# Audio_Video_Router.net
KiCad netlist of a schematic drawn in Altium Designer
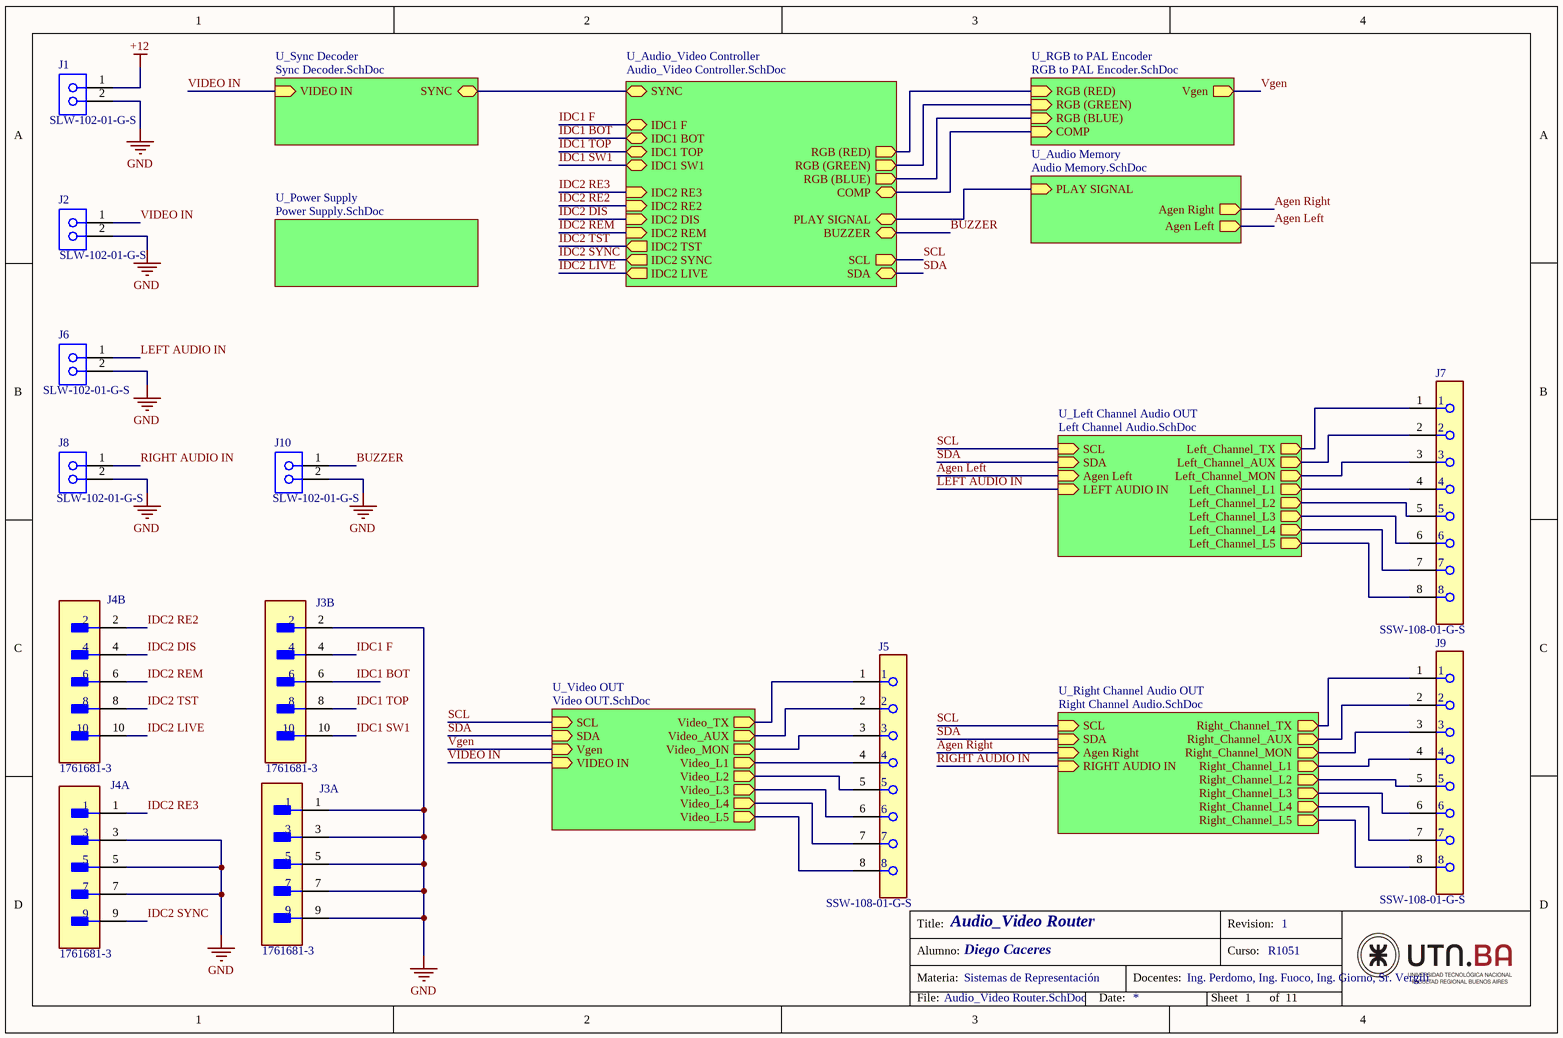
[diagram p0: Audio_Video Router.SchDoc]

(export (version "E")
  (design (tool "Eeschema 10.0.6"))
  (components
    (comp (ref "J1")
      (value "SLW-102-01-G-S")
      (footprint "SMTC-SLW-102-01-X-S")
      (fields (field (name "MANUFACTURER") "Samtec"))
      (libsource (lib "Altium Content Vault") (part "SMTC-SLW-102-01-X-S"))
    )
    (comp (ref "J2")
      (value "SLW-102-01-G-S")
      (footprint "SMTC-SLW-102-01-X-S")
      (fields (field (name "MANUFACTURER") "Samtec"))
      (libsource (lib "Altium Content Vault") (part "SMTC-SLW-102-01-X-S"))
    )
    (comp (ref "J3")
      (value "1761681-3")
      (footprint "FP-1761681-3-MFG")
      (description "1761681-3 Conn Shrouded Header (4 Sides) HDR 10 POS 2.54mm Solder ST Top Entry Thru-Hole Tray")
      (libsource (lib "Altium Content Vault") (part "544f42128f4185dcb88ce1ce9bf1982"))
    )
    (comp (ref "J4")
      (value "1761681-3")
      (footprint "FP-1761681-3-MFG")
      (description "1761681-3 Conn Shrouded Header (4 Sides) HDR 10 POS 2.54mm Solder ST Top Entry Thru-Hole Tray")
      (libsource (lib "Altium Content Vault") (part "544f42128f4185dcb88ce1ce9bf1982"))
    )
    (comp (ref "J5")
      (value "SSW-108-01-G-S")
      (footprint "FP-SSW-108-01-G-S-MFG")
      (description "CONN RCPT 8POS 0.1 GOLD PCB")
      (libsource (lib "Altium Content Vault") (part "a32a9c29f5c2290c50060dfb8ad7212"))
    )
    (comp (ref "J6")
      (value "SLW-102-01-G-S")
      (footprint "SMTC-SLW-102-01-X-S")
      (fields (field (name "MANUFACTURER") "Samtec"))
      (libsource (lib "Altium Content Vault") (part "SMTC-SLW-102-01-X-S"))
    )
    (comp (ref "J7")
      (value "SSW-108-01-G-S")
      (footprint "FP-SSW-108-01-G-S-MFG")
      (description "CONN RCPT 8POS 0.1 GOLD PCB")
      (libsource (lib "Altium Content Vault") (part "a32a9c29f5c2290c50060dfb8ad7212"))
    )
    (comp (ref "J8")
      (value "SLW-102-01-G-S")
      (footprint "SMTC-SLW-102-01-X-S")
      (fields (field (name "MANUFACTURER") "Samtec"))
      (libsource (lib "Altium Content Vault") (part "SMTC-SLW-102-01-X-S"))
    )
    (comp (ref "J9")
      (value "SSW-108-01-G-S")
      (footprint "FP-SSW-108-01-G-S-MFG")
      (description "CONN RCPT 8POS 0.1 GOLD PCB")
      (libsource (lib "Altium Content Vault") (part "a32a9c29f5c2290c50060dfb8ad7212"))
    )
    (comp (ref "J10")
      (value "SLW-102-01-G-S")
      (footprint "SMTC-SLW-102-01-X-S")
      (fields (field (name "MANUFACTURER") "Samtec"))
      (libsource (lib "Altium Content Vault") (part "SMTC-SLW-102-01-X-S"))
    )
  )
  (nets
    (net (code "1") (name "+12") (class "Default")
      (node (ref "J1") (pin "1") (pinfunction "1_1") (pintype "passive"))
    )
    (net (code "4") (name "/BUZZER") (class "Default")
      (node (ref "J10") (pin "1") (pinfunction "1_1") (pintype "passive"))
    )
    (net (code "6") (name "/IDC1 BOT") (class "Default")
      (node (ref "J3") (pin "6") (pinfunction "6_6") (pintype "passive"))
    )
    (net (code "7") (name "/IDC1 F") (class "Default")
      (node (ref "J3") (pin "4") (pinfunction "4_4") (pintype "passive"))
    )
    (net (code "8") (name "/IDC1 SW1") (class "Default")
      (node (ref "J3") (pin "10") (pinfunction "10_10") (pintype "passive"))
    )
    (net (code "9") (name "/IDC1 TOP") (class "Default")
      (node (ref "J3") (pin "8") (pinfunction "8_8") (pintype "passive"))
    )
    (net (code "10") (name "/IDC2 DIS") (class "Default")
      (node (ref "J4") (pin "4") (pinfunction "4_4") (pintype "passive"))
    )
    (net (code "11") (name "/IDC2 LIVE") (class "Default")
      (node (ref "J4") (pin "10") (pinfunction "10_10") (pintype "passive"))
    )
    (net (code "12") (name "/IDC2 RE2") (class "Default")
      (node (ref "J4") (pin "2") (pinfunction "2_2") (pintype "passive"))
    )
    (net (code "13") (name "/IDC2 RE3") (class "Default")
      (node (ref "J4") (pin "1") (pinfunction "1_1") (pintype "passive"))
    )
    (net (code "14") (name "/IDC2 REM") (class "Default")
      (node (ref "J4") (pin "6") (pinfunction "6_6") (pintype "passive"))
    )
    (net (code "15") (name "/IDC2 SYNC") (class "Default")
      (node (ref "J4") (pin "9") (pinfunction "9_9") (pintype "passive"))
    )
    (net (code "16") (name "/IDC2 TST") (class "Default")
      (node (ref "J4") (pin "8") (pinfunction "8_8") (pintype "passive"))
    )
    (net (code "17") (name "/LEFT AUDIO IN") (class "Default")
      (node (ref "J6") (pin "1") (pinfunction "1_1") (pintype "passive"))
    )
    (net (code "18") (name "/Left_Channel_AUX") (class "Default")
      (node (ref "J7") (pin "2") (pinfunction "2_2") (pintype "passive"))
    )
    (net (code "19") (name "/Left_Channel_L1") (class "Default")
      (node (ref "J7") (pin "4") (pinfunction "4_4") (pintype "passive"))
    )
    (net (code "20") (name "/Left_Channel_L2") (class "Default")
      (node (ref "J7") (pin "5") (pinfunction "5_5") (pintype "passive"))
    )
    (net (code "21") (name "/Left_Channel_L3") (class "Default")
      (node (ref "J7") (pin "6") (pinfunction "6_6") (pintype "passive"))
    )
    (net (code "22") (name "/Left_Channel_L4") (class "Default")
      (node (ref "J7") (pin "7") (pinfunction "7_7") (pintype "passive"))
    )
    (net (code "23") (name "/Left_Channel_L5") (class "Default")
      (node (ref "J7") (pin "8") (pinfunction "8_8") (pintype "passive"))
    )
    (net (code "24") (name "/Left_Channel_MON") (class "Default")
      (node (ref "J7") (pin "3") (pinfunction "3_3") (pintype "passive"))
    )
    (net (code "25") (name "/Left_Channel_TX") (class "Default")
      (node (ref "J7") (pin "1") (pinfunction "1_1") (pintype "passive"))
    )
    (net (code "30") (name "/RIGHT AUDIO IN") (class "Default")
      (node (ref "J8") (pin "1") (pinfunction "1_1") (pintype "passive"))
    )
    (net (code "31") (name "/Right_Channel_AUX") (class "Default")
      (node (ref "J9") (pin "2") (pinfunction "2_2") (pintype "passive"))
    )
    (net (code "32") (name "/Right_Channel_L1") (class "Default")
      (node (ref "J9") (pin "4") (pinfunction "4_4") (pintype "passive"))
    )
    (net (code "33") (name "/Right_Channel_L2") (class "Default")
      (node (ref "J9") (pin "5") (pinfunction "5_5") (pintype "passive"))
    )
    (net (code "34") (name "/Right_Channel_L3") (class "Default")
      (node (ref "J9") (pin "6") (pinfunction "6_6") (pintype "passive"))
    )
    (net (code "35") (name "/Right_Channel_L4") (class "Default")
      (node (ref "J9") (pin "7") (pinfunction "7_7") (pintype "passive"))
    )
    (net (code "36") (name "/Right_Channel_L5") (class "Default")
      (node (ref "J9") (pin "8") (pinfunction "8_8") (pintype "passive"))
    )
    (net (code "37") (name "/Right_Channel_MON") (class "Default")
      (node (ref "J9") (pin "3") (pinfunction "3_3") (pintype "passive"))
    )
    (net (code "38") (name "/Right_Channel_TX") (class "Default")
      (node (ref "J9") (pin "1") (pinfunction "1_1") (pintype "passive"))
    )
    (net (code "42") (name "/VIDEO IN") (class "Default")
      (node (ref "J2") (pin "1") (pinfunction "1_1") (pintype "passive"))
    )
    (net (code "44") (name "/Video_AUX") (class "Default")
      (node (ref "J5") (pin "2") (pinfunction "2_2") (pintype "passive"))
    )
    (net (code "45") (name "/Video_L1") (class "Default")
      (node (ref "J5") (pin "4") (pinfunction "4_4") (pintype "passive"))
    )
    (net (code "46") (name "/Video_L2") (class "Default")
      (node (ref "J5") (pin "5") (pinfunction "5_5") (pintype "passive"))
    )
    (net (code "47") (name "/Video_L3") (class "Default")
      (node (ref "J5") (pin "6") (pinfunction "6_6") (pintype "passive"))
    )
    (net (code "48") (name "/Video_L4") (class "Default")
      (node (ref "J5") (pin "7") (pinfunction "7_7") (pintype "passive"))
    )
    (net (code "49") (name "/Video_L5") (class "Default")
      (node (ref "J5") (pin "8") (pinfunction "8_8") (pintype "passive"))
    )
    (net (code "50") (name "/Video_MON") (class "Default")
      (node (ref "J5") (pin "3") (pinfunction "3_3") (pintype "passive"))
    )
    (net (code "51") (name "/Video_TX") (class "Default")
      (node (ref "J5") (pin "1") (pinfunction "1_1") (pintype "passive"))
    )
    (net (code "52") (name "GND") (class "Default")
      (node (ref "J1") (pin "2") (pinfunction "2_2") (pintype "passive"))
      (node (ref "J10") (pin "2") (pinfunction "2_2") (pintype "passive"))
      (node (ref "J2") (pin "2") (pinfunction "2_2") (pintype "passive"))
      (node (ref "J3") (pin "1") (pinfunction "1_1") (pintype "passive"))
      (node (ref "J3") (pin "2") (pinfunction "2_2") (pintype "passive"))
      (node (ref "J3") (pin "3") (pinfunction "3_3") (pintype "passive"))
      (node (ref "J3") (pin "5") (pinfunction "5_5") (pintype "passive"))
      (node (ref "J3") (pin "7") (pinfunction "7_7") (pintype "passive"))
      (node (ref "J3") (pin "9") (pinfunction "9_9") (pintype "passive"))
      (node (ref "J4") (pin "3") (pinfunction "3_3") (pintype "passive"))
      (node (ref "J4") (pin "5") (pinfunction "5_5") (pintype "passive"))
      (node (ref "J4") (pin "7") (pinfunction "7_7") (pintype "passive"))
      (node (ref "J6") (pin "2") (pinfunction "2_2") (pintype "passive"))
      (node (ref "J8") (pin "2") (pinfunction "2_2") (pintype "passive"))
    )
  )
)
